# ESP8266.net
KiCad netlist of a schematic drawn in Altium Designer
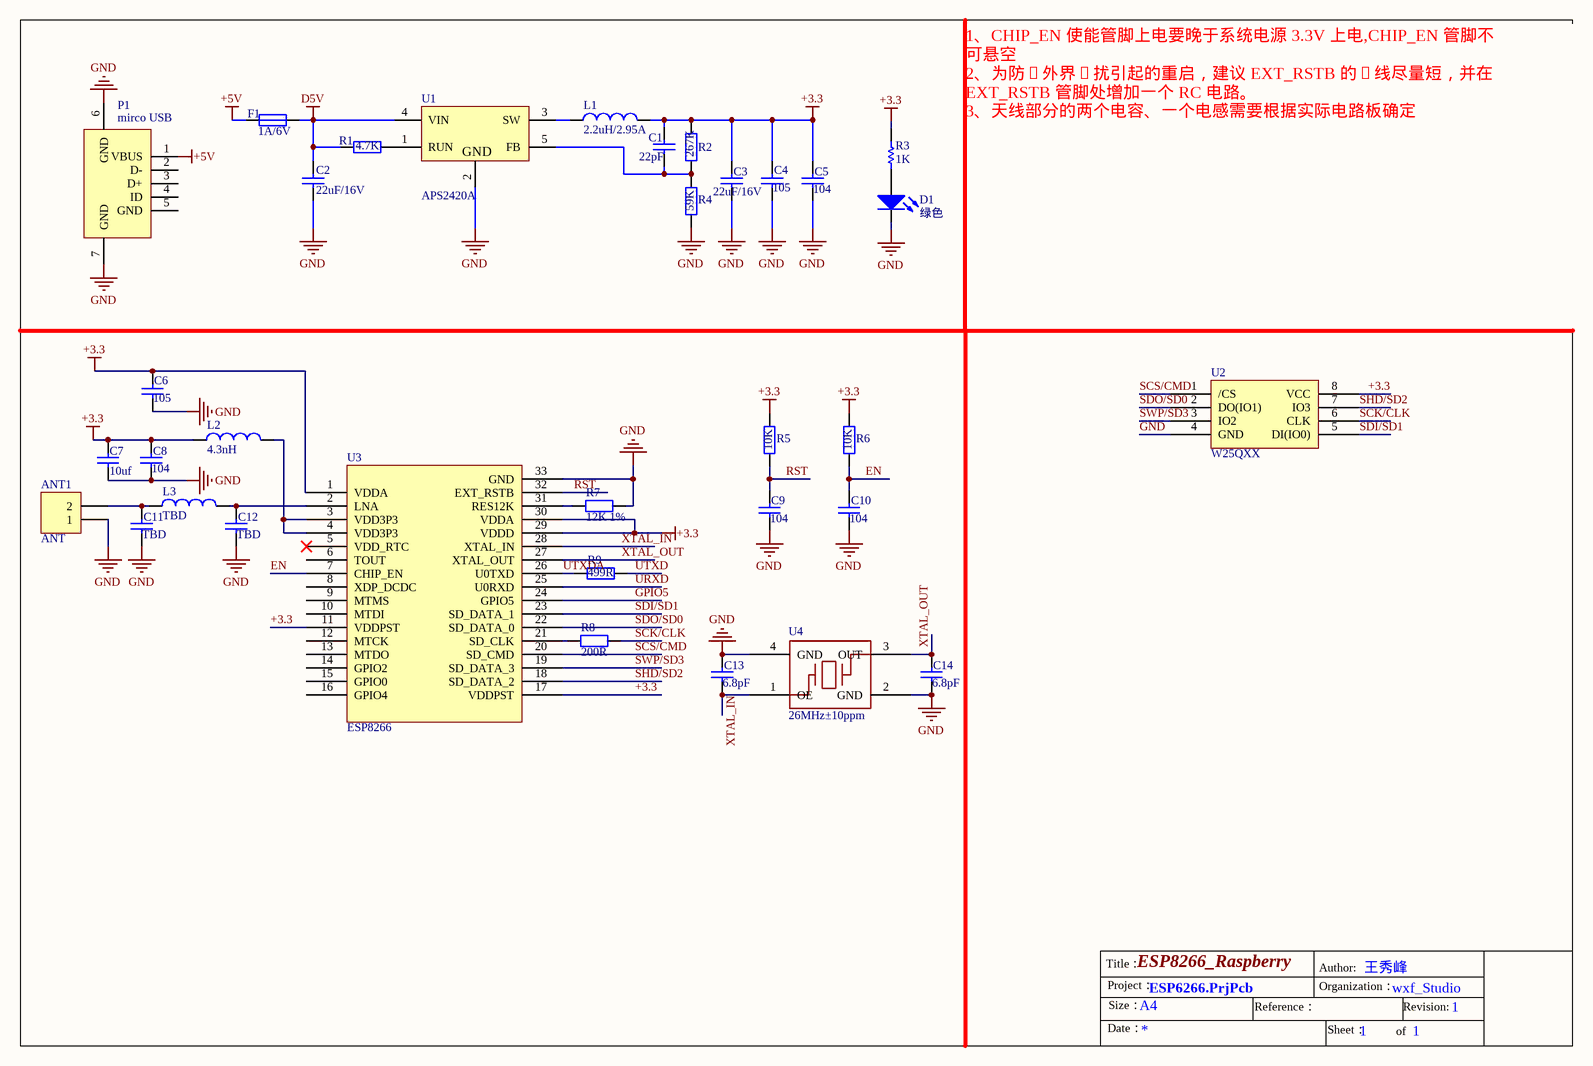
[diagram p0: ESP8266.SchDoc]

(export (version "E")
  (design (tool "Eeschema 10.0.6"))
  (components
    (comp (ref "ANT1")
      (value "ANT")
      (footprint "HDR1X2")
      (description "Header, 2-Pin")
      (fields (field (name "PUBLISHER") "Altium Limited"))
      (libsource (lib "Miscellaneous Connectors") (part "Header 2"))
    )
    (comp (ref "C1")
      (value "22pF")
      (footprint "0603_C")
      (description "无极性电容")
      (libsource (lib "DJX_SCH_NEW") (part "Cap_Nonpolar"))
    )
    (comp (ref "C2")
      (value "22uF/16V")
      (footprint "1206_C")
      (description "无极性电容")
      (libsource (lib "DJX_SCH_NEW") (part "Cap_Nonpolar"))
    )
    (comp (ref "C3")
      (value "22uF/16V")
      (footprint "1206_C")
      (description "无极性电容")
      (libsource (lib "DJX_SCH_NEW") (part "Cap_Nonpolar"))
    )
    (comp (ref "C4")
      (value "105")
      (footprint "0603_C")
      (description "无极性电容")
      (libsource (lib "DJX_SCH_NEW") (part "Cap_Nonpolar"))
    )
    (comp (ref "C5")
      (value "104")
      (footprint "0603_C")
      (description "无极性电容")
      (libsource (lib "DJX_SCH_NEW") (part "Cap_Nonpolar"))
    )
    (comp (ref "C6")
      (value "105")
      (footprint "0603_C")
      (description "无极性电容")
      (libsource (lib "DJX_SCH_NEW") (part "Cap_Nonpolar"))
    )
    (comp (ref "C7")
      (value "10uf")
      (footprint "1206_C")
      (description "无极性电容")
      (libsource (lib "DJX_SCH_NEW") (part "Cap_Nonpolar"))
    )
    (comp (ref "C8")
      (value "104")
      (footprint "0603_C")
      (description "无极性电容")
      (libsource (lib "DJX_SCH_NEW") (part "Cap_Nonpolar"))
    )
    (comp (ref "C9")
      (value "104")
      (footprint "0603_C")
      (description "无极性电容")
      (libsource (lib "DJX_SCH_NEW") (part "Cap_Nonpolar"))
    )
    (comp (ref "C10")
      (value "104")
      (footprint "0603_C")
      (description "无极性电容")
      (libsource (lib "DJX_SCH_NEW") (part "Cap_Nonpolar"))
    )
    (comp (ref "C11")
      (value "TBD")
      (footprint "0603_C")
      (description "无极性电容")
      (libsource (lib "DJX_SCH_NEW") (part "Cap_Nonpolar"))
    )
    (comp (ref "C12")
      (value "TBD")
      (footprint "0603_C")
      (description "无极性电容")
      (libsource (lib "DJX_SCH_NEW") (part "Cap_Nonpolar"))
    )
    (comp (ref "C13")
      (value "6.8pF")
      (footprint "0603_C")
      (description "无极性电容")
      (libsource (lib "DJX_SCH_NEW") (part "Cap_Nonpolar"))
    )
    (comp (ref "C14")
      (value "6.8pF")
      (footprint "0603_C")
      (description "无极性电容")
      (libsource (lib "DJX_SCH_NEW") (part "Cap_Nonpolar"))
    )
    (comp (ref "D1")
      (value "绿色")
      (footprint "0603_LED_S1")
      (description "绿色LED")
      (libsource (lib "DJX_SCH_NEW") (part "LED-G"))
    )
    (comp (ref "F1")
      (value "1A/6V")
      (footprint "1206_R")
      (description "自恢复保险丝")
      (libsource (lib "DJX_SCH_NEW") (part "FUSE"))
    )
    (comp (ref "L1")
      (value "2.2uH/2.95A")
      (footprint "4030")
      (description "电感")
      (libsource (lib "DJX_SCH_NEW") (part "Inductor"))
    )
    (comp (ref "L2")
      (value "4.3nH")
      (footprint "0402-A")
      (description "Inductor")
      (libsource (lib "Miscellaneous Devices") (part "Inductor"))
    )
    (comp (ref "L3")
      (value "TBD")
      (footprint "0402-A")
      (description "Inductor")
      (libsource (lib "Miscellaneous Devices") (part "Inductor"))
    )
    (comp (ref "P1")
      (value "mirco USB")
      (footprint "micro USB 贴")
      (description "mirco  USB 立")
      (libsource (lib "spss_intlib") (part "Micro USB"))
    )
    (comp (ref "R1") (value "4.7K") (footprint "0603_R") (libsource (lib "") (part "Res_1")))
    (comp (ref "R2") (value "267K") (footprint "0603_R") (libsource (lib "DJX_SCH_NEW") (part "Res")))
    (comp (ref "R3")
      (value "1K")
      (footprint "Miscellaneous Devices LC:0603_R")
      (description "Resistor")
      (libsource (lib "Miscellaneous Devices") (part "Res1"))
    )
    (comp (ref "R4") (value "59K") (footprint "0603_R") (libsource (lib "DJX_SCH_NEW") (part "Res")))
    (comp (ref "R5") (value "10K") (footprint "0603_R") (libsource (lib "DJX_SCH_NEW") (part "Res")))
    (comp (ref "R6") (value "10K") (footprint "0603_R") (libsource (lib "DJX_SCH_NEW") (part "Res")))
    (comp (ref "R7") (value "12K 1%") (footprint "0603_R") (libsource (lib "") (part "Res_1")))
    (comp (ref "R8") (value "200R") (footprint "0603_R") (libsource (lib "") (part "Res_1")))
    (comp (ref "R9") (value "499R") (footprint "0603_R") (libsource (lib "") (part "Res_1")))
    (comp (ref "U1")
      (value "APS2420A")
      (footprint "SOT-23-5")
      (libsource (lib "DJX_SCH_NEW") (part "APS2420A"))
    )
    (comp (ref "U2")
      (value "W25QXX")
      (footprint "SOIC-8_208mil")
      (libsource (lib "ESP6266Lib") (part "W25QXX"))
    )
    (comp (ref "U3")
      (value "ESP8266")
      (footprint "ESP8266EX")
      (libsource (lib "ESP6266Lib") (part "ESP8266"))
    )
    (comp (ref "U4")
      (value "26MHz±10ppm")
      (footprint "3225")
      (libsource (lib "ESP8266Lib") (part "26MHz±10ppm"))
    )
  )
  (nets
    (net (code "1") (name "+3.3") (class "Default")
      (node (ref "C1") (pin "2") (pinfunction "2_2") (pintype "passive"))
      (node (ref "C3") (pin "2") (pinfunction "2_2") (pintype "passive"))
      (node (ref "C4") (pin "2") (pinfunction "2_2") (pintype "passive"))
      (node (ref "C5") (pin "2") (pinfunction "2_2") (pintype "passive"))
      (node (ref "C6") (pin "2") (pinfunction "2_2") (pintype "passive"))
      (node (ref "C7") (pin "2") (pinfunction "2_2") (pintype "passive"))
      (node (ref "C8") (pin "2") (pinfunction "2_2") (pintype "passive"))
      (node (ref "L1") (pin "2") (pinfunction "2_2") (pintype "passive"))
      (node (ref "L2") (pin "1") (pinfunction "1_1") (pintype "passive"))
      (node (ref "R2") (pin "1") (pinfunction "1_1") (pintype "passive"))
      (node (ref "R3") (pin "1") (pinfunction "1_1") (pintype "passive"))
      (node (ref "R5") (pin "1") (pinfunction "1_1") (pintype "passive"))
      (node (ref "R6") (pin "1") (pinfunction "1_1") (pintype "passive"))
      (node (ref "U2") (pin "8") (pinfunction "VCC_8") (pintype "passive"))
      (node (ref "U3") (pin "1") (pinfunction "VDDA_1") (pintype "passive"))
      (node (ref "U3") (pin "11") (pinfunction "VDDPST_11") (pintype "passive"))
      (node (ref "U3") (pin "17") (pinfunction "VDDPST_17") (pintype "passive"))
      (node (ref "U3") (pin "29") (pinfunction "VDDD_29") (pintype "passive"))
      (node (ref "U3") (pin "30") (pinfunction "VDDA_30") (pintype "passive"))
    )
    (net (code "2") (name "+5V") (class "Default")
      (node (ref "F1") (pin "1") (pinfunction "1_1") (pintype "passive"))
      (node (ref "P1") (pin "1") (pinfunction "VBUS_1") (pintype "passive"))
    )
    (net (code "3") (name "/EN") (class "Default")
      (node (ref "C10") (pin "2") (pinfunction "2_2") (pintype "passive"))
      (node (ref "R6") (pin "2") (pinfunction "2_2") (pintype "passive"))
      (node (ref "U3") (pin "7") (pinfunction "CHIP_EN_7") (pintype "passive"))
    )
    (net (code "4") (name "/GPIO5") (class "Default")
      (node (ref "U3") (pin "24") (pinfunction "GPIO5_24") (pintype "passive"))
    )
    (net (code "5") (name "/RST") (class "Default")
      (node (ref "C9") (pin "2") (pinfunction "2_2") (pintype "passive"))
      (node (ref "R5") (pin "2") (pinfunction "2_2") (pintype "passive"))
      (node (ref "U3") (pin "32") (pinfunction "EXT_RSTB_32") (pintype "passive"))
    )
    (net (code "6") (name "/SCK{slash}CLK") (class "Default")
      (node (ref "R8") (pin "2") (pinfunction "2_2") (pintype "passive"))
      (node (ref "U2") (pin "6") (pinfunction "CLK_6") (pintype "passive"))
    )
    (net (code "7") (name "/SCS{slash}CMD") (class "Default")
      (node (ref "U2") (pin "1") (pinfunction "/CS_1") (pintype "passive"))
      (node (ref "U3") (pin "20") (pinfunction "SD_CMD_20") (pintype "passive"))
    )
    (net (code "8") (name "/SDI{slash}SD1") (class "Default")
      (node (ref "U2") (pin "5") (pinfunction "DI(IO0)_5") (pintype "passive"))
      (node (ref "U3") (pin "23") (pinfunction "SD_DATA_1_23") (pintype "passive"))
    )
    (net (code "9") (name "/SDO{slash}SD0") (class "Default")
      (node (ref "U2") (pin "2") (pinfunction "DO(IO1)_2") (pintype "passive"))
      (node (ref "U3") (pin "22") (pinfunction "SD_DATA_0_22") (pintype "passive"))
    )
    (net (code "10") (name "/SHD{slash}SD2") (class "Default")
      (node (ref "U2") (pin "7") (pinfunction "IO3_7") (pintype "passive"))
      (node (ref "U3") (pin "18") (pinfunction "SD_DATA_2_18") (pintype "passive"))
    )
    (net (code "11") (name "/SWP{slash}SD3") (class "Default")
      (node (ref "U2") (pin "3") (pinfunction "IO2_3") (pintype "passive"))
      (node (ref "U3") (pin "19") (pinfunction "SD_DATA_3_19") (pintype "passive"))
    )
    (net (code "12") (name "/URXD") (class "Default")
      (node (ref "U3") (pin "25") (pinfunction "U0RXD_25") (pintype "passive"))
    )
    (net (code "13") (name "/UTXD") (class "Default")
      (node (ref "R9") (pin "2") (pinfunction "2_2") (pintype "passive"))
    )
    (net (code "14") (name "/UTXDA") (class "Default")
      (node (ref "R9") (pin "1") (pinfunction "1_1") (pintype "passive"))
      (node (ref "U3") (pin "26") (pinfunction "U0TXD_26") (pintype "passive"))
    )
    (net (code "15") (name "/XTAL_IN") (class "Default")
      (node (ref "C13") (pin "1") (pinfunction "1_1") (pintype "passive"))
      (node (ref "U3") (pin "28") (pinfunction "XTAL_IN_28") (pintype "passive"))
      (node (ref "U4") (pin "1") (pinfunction "OE_1") (pintype "passive"))
    )
    (net (code "16") (name "/XTAL_OUT") (class "Default")
      (node (ref "C14") (pin "2") (pinfunction "2_2") (pintype "passive"))
      (node (ref "U3") (pin "27") (pinfunction "XTAL_OUT_27") (pintype "passive"))
      (node (ref "U4") (pin "3") (pinfunction "OUT_3") (pintype "passive"))
    )
    (net (code "17") (name "D5V") (class "Default")
      (node (ref "C2") (pin "2") (pinfunction "2_2") (pintype "passive"))
      (node (ref "F1") (pin "2") (pinfunction "2_2") (pintype "passive"))
      (node (ref "R1") (pin "1") (pinfunction "1_1") (pintype "passive"))
      (node (ref "U1") (pin "4") (pinfunction "VIN_4") (pintype "passive"))
    )
    (net (code "18") (name "GND") (class "Default")
      (node (ref "ANT1") (pin "1") (pinfunction "1_1") (pintype "passive"))
      (node (ref "C10") (pin "1") (pinfunction "1_1") (pintype "passive"))
      (node (ref "C11") (pin "1") (pinfunction "1_1") (pintype "passive"))
      (node (ref "C12") (pin "1") (pinfunction "1_1") (pintype "passive"))
      (node (ref "C13") (pin "2") (pinfunction "2_2") (pintype "passive"))
      (node (ref "C14") (pin "1") (pinfunction "1_1") (pintype "passive"))
      (node (ref "C2") (pin "1") (pinfunction "1_1") (pintype "passive"))
      (node (ref "C3") (pin "1") (pinfunction "1_1") (pintype "passive"))
      (node (ref "C4") (pin "1") (pinfunction "1_1") (pintype "passive"))
      (node (ref "C5") (pin "1") (pinfunction "1_1") (pintype "passive"))
      (node (ref "C6") (pin "1") (pinfunction "1_1") (pintype "passive"))
      (node (ref "C7") (pin "1") (pinfunction "1_1") (pintype "passive"))
      (node (ref "C8") (pin "1") (pinfunction "1_1") (pintype "passive"))
      (node (ref "C9") (pin "1") (pinfunction "1_1") (pintype "passive"))
      (node (ref "D1") (pin "2") (pinfunction "K_2") (pintype "passive"))
      (node (ref "P1") (pin "6") (pinfunction "GND_6") (pintype "passive"))
      (node (ref "P1") (pin "7") (pinfunction "GND_7") (pintype "passive"))
      (node (ref "R4") (pin "2") (pinfunction "2_2") (pintype "passive"))
      (node (ref "R7") (pin "2") (pinfunction "2_2") (pintype "passive"))
      (node (ref "U1") (pin "2") (pinfunction "GND_2") (pintype "passive"))
      (node (ref "U2") (pin "4") (pinfunction "GND_4") (pintype "passive"))
      (node (ref "U3") (pin "33") (pinfunction "GND_33") (pintype "passive"))
      (node (ref "U4") (pin "2") (pinfunction "GND_2") (pintype "passive"))
      (node (ref "U4") (pin "4") (pinfunction "GND_4") (pintype "passive"))
    )
    (net (code "19") (name "Net-(ANT1-Pad2)") (class "Default")
      (node (ref "ANT1") (pin "2") (pinfunction "2_2") (pintype "passive"))
      (node (ref "C11") (pin "2") (pinfunction "2_2") (pintype "passive"))
      (node (ref "L3") (pin "1") (pinfunction "1_1") (pintype "passive"))
    )
    (net (code "20") (name "Net-(D1-A)") (class "Default")
      (node (ref "D1") (pin "1") (pinfunction "A_1") (pintype "passive"))
      (node (ref "R3") (pin "2") (pinfunction "2_2") (pintype "passive"))
    )
    (net (code "21") (name "Net-(L2-Pad2)") (class "Default")
      (node (ref "L2") (pin "2") (pinfunction "2_2") (pintype "passive"))
      (node (ref "U3") (pin "3") (pinfunction "VDD3P3_3") (pintype "passive"))
      (node (ref "U3") (pin "4") (pinfunction "VDD3P3_4") (pintype "passive"))
    )
    (net (code "22") (name "Net-(U1-FB)") (class "Default")
      (node (ref "C1") (pin "1") (pinfunction "1_1") (pintype "passive"))
      (node (ref "R2") (pin "2") (pinfunction "2_2") (pintype "passive"))
      (node (ref "R4") (pin "1") (pinfunction "1_1") (pintype "passive"))
      (node (ref "U1") (pin "5") (pinfunction "FB_5") (pintype "passive"))
    )
    (net (code "23") (name "Net-(U1-RUN)") (class "Default")
      (node (ref "R1") (pin "2") (pinfunction "2_2") (pintype "passive"))
      (node (ref "U1") (pin "1") (pinfunction "RUN_1") (pintype "passive"))
    )
    (net (code "24") (name "Net-(U1-SW)") (class "Default")
      (node (ref "L1") (pin "1") (pinfunction "1_1") (pintype "passive"))
      (node (ref "U1") (pin "3") (pinfunction "SW_3") (pintype "passive"))
    )
    (net (code "25") (name "Net-(U3-LNA)") (class "Default")
      (node (ref "C12") (pin "2") (pinfunction "2_2") (pintype "passive"))
      (node (ref "L3") (pin "2") (pinfunction "2_2") (pintype "passive"))
      (node (ref "U3") (pin "2") (pinfunction "LNA_2") (pintype "passive"))
    )
    (net (code "26") (name "Net-(U3-RES12K)") (class "Default")
      (node (ref "R7") (pin "1") (pinfunction "1_1") (pintype "passive"))
      (node (ref "U3") (pin "31") (pinfunction "RES12K_31") (pintype "passive"))
    )
    (net (code "27") (name "Net-(U3-SD_CLK)") (class "Default")
      (node (ref "R8") (pin "1") (pinfunction "1_1") (pintype "passive"))
      (node (ref "U3") (pin "21") (pinfunction "SD_CLK_21") (pintype "passive"))
    )
    (net (code "28") (name "unconnected-(P1-D+-Pad3)") (class "Default")
      (node (ref "P1") (pin "3") (pinfunction "D+_3") (pintype "passive"))
    )
    (net (code "29") (name "unconnected-(P1-D--Pad2)") (class "Default")
      (node (ref "P1") (pin "2") (pinfunction "D-_2") (pintype "passive"))
    )
    (net (code "30") (name "unconnected-(P1-GND-Pad5)") (class "Default")
      (node (ref "P1") (pin "5") (pinfunction "GND_5") (pintype "passive"))
    )
    (net (code "31") (name "unconnected-(P1-ID-Pad4)") (class "Default")
      (node (ref "P1") (pin "4") (pinfunction "ID_4") (pintype "passive"))
    )
    (net (code "32") (name "unconnected-(U3-GPIO0-Pad15)") (class "Default")
      (node (ref "U3") (pin "15") (pinfunction "GPIO0_15") (pintype "passive"))
    )
    (net (code "33") (name "unconnected-(U3-GPIO2-Pad14)") (class "Default")
      (node (ref "U3") (pin "14") (pinfunction "GPIO2_14") (pintype "passive"))
    )
    (net (code "34") (name "unconnected-(U3-GPIO4-Pad16)") (class "Default")
      (node (ref "U3") (pin "16") (pinfunction "GPIO4_16") (pintype "passive"))
    )
    (net (code "35") (name "unconnected-(U3-MTCK-Pad12)") (class "Default")
      (node (ref "U3") (pin "12") (pinfunction "MTCK_12") (pintype "passive"))
    )
    (net (code "36") (name "unconnected-(U3-MTDI-Pad10)") (class "Default")
      (node (ref "U3") (pin "10") (pinfunction "MTDI_10") (pintype "passive"))
    )
    (net (code "37") (name "unconnected-(U3-MTDO-Pad13)") (class "Default")
      (node (ref "U3") (pin "13") (pinfunction "MTDO_13") (pintype "passive"))
    )
    (net (code "38") (name "unconnected-(U3-MTMS-Pad9)") (class "Default")
      (node (ref "U3") (pin "9") (pinfunction "MTMS_9") (pintype "passive"))
    )
    (net (code "39") (name "unconnected-(U3-TOUT-Pad6)") (class "Default")
      (node (ref "U3") (pin "6") (pinfunction "TOUT_6") (pintype "passive"))
    )
    (net (code "40") (name "unconnected-(U3-VDD_RTC-Pad5)") (class "Default")
      (node (ref "U3") (pin "5") (pinfunction "VDD_RTC_5") (pintype "passive+no_connect"))
    )
    (net (code "41") (name "unconnected-(U3-XDP_DCDC-Pad8)") (class "Default")
      (node (ref "U3") (pin "8") (pinfunction "XDP_DCDC_8") (pintype "passive"))
    )
  )
)
